# SCT2XX0_STEP-DOWM.net
KiCad netlist of a schematic drawn in Altium Designer
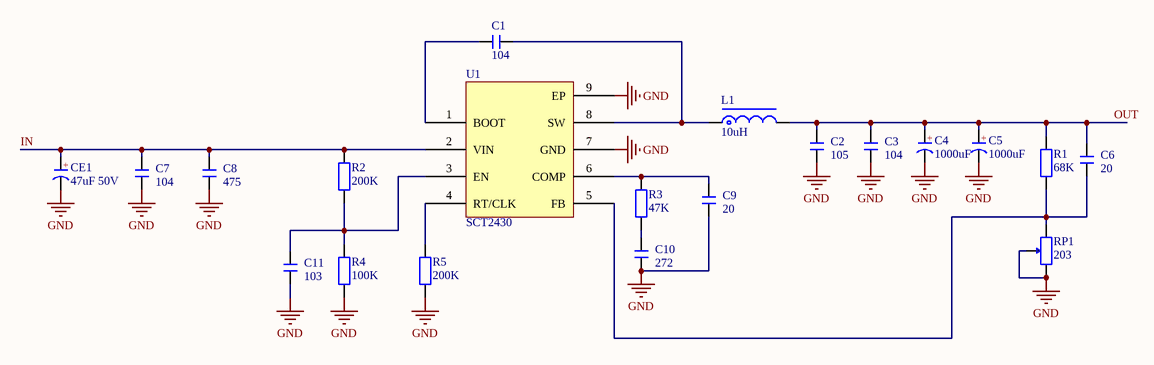
[diagram p0: SCT2XX0 STEP-DOWM.SchDoc]

(export (version "E")
  (design (tool "Eeschema 10.0.6"))
  (components
    (comp (ref "C1")
      (value "104")
      (footprint "C 0805_L")
      (description "贴片电容")
      (libsource (lib "01 - 电容-电阻-电感") (part "C"))
    )
    (comp (ref "C2")
      (value "105")
      (footprint "C 0805_L")
      (description "贴片电容")
      (libsource (lib "01 - 电容-电阻-电感") (part "C"))
    )
    (comp (ref "C3")
      (value "104")
      (footprint "C 0805_L")
      (description "贴片电容")
      (libsource (lib "01 - 电容-电阻-电感") (part "C"))
    )
    (comp (ref "C4")
      (value "1000uF")
      (footprint "CAP 7.5*16*25")
      (description "直插电解电容")
      (libsource (lib "01 - 电容-电阻-电感") (part "CE"))
    )
    (comp (ref "C5")
      (value "1000uF")
      (footprint "CAP 5.0*12.5*20")
      (description "直插电解电容")
      (libsource (lib "01 - 电容-电阻-电感") (part "CE"))
    )
    (comp (ref "C6")
      (value "20")
      (footprint "C 0805_L")
      (description "贴片电容")
      (libsource (lib "01 - 电容-电阻-电感") (part "C"))
    )
    (comp (ref "C7")
      (value "104")
      (footprint "C 0805_L")
      (description "贴片电容")
      (libsource (lib "01 - 电容-电阻-电感") (part "C"))
    )
    (comp (ref "C8")
      (value "475")
      (footprint "C 0805_L")
      (description "贴片电容")
      (libsource (lib "01 - 电容-电阻-电感") (part "C"))
    )
    (comp (ref "C9")
      (value "20")
      (footprint "C 0805_L")
      (description "贴片电容")
      (libsource (lib "01 - 电容-电阻-电感") (part "C"))
    )
    (comp (ref "C10")
      (value "272")
      (footprint "C 0805_L")
      (description "贴片电容")
      (libsource (lib "01 - 电容-电阻-电感") (part "C"))
    )
    (comp (ref "C11")
      (value "103")
      (footprint "C 0805_L")
      (description "贴片电容")
      (libsource (lib "01 - 电容-电阻-电感") (part "C"))
    )
    (comp (ref "CE1")
      (value "47uF 50V")
      (footprint "CM C(5*5.4)")
      (description "贴片电解电容")
      (libsource (lib "01 - 电容-电阻-电感") (part "CE_SMD"))
    )
    (comp (ref "L1")
      (value "10uH")
      (footprint "CDRH127")
      (description "功率屏蔽电感")
      (libsource (lib "01 - 电容-电阻-电感") (part "L-CDRH"))
    )
    (comp (ref "R1")
      (value "68K")
      (footprint "R 0805_L")
      (description "贴片电阻")
      (libsource (lib "01 - 电容-电阻-电感") (part "R"))
    )
    (comp (ref "R2")
      (value "200K")
      (footprint "R 0805_L")
      (description "贴片电阻")
      (libsource (lib "01 - 电容-电阻-电感") (part "R"))
    )
    (comp (ref "R3")
      (value "47K")
      (footprint "R 0805_L")
      (description "贴片电阻")
      (libsource (lib "01 - 电容-电阻-电感") (part "R"))
    )
    (comp (ref "R4")
      (value "100K")
      (footprint "R 0805_L")
      (description "贴片电阻")
      (libsource (lib "01 - 电容-电阻-电感") (part "R"))
    )
    (comp (ref "R5")
      (value "200K")
      (footprint "R 0805_L")
      (description "贴片电阻")
      (libsource (lib "01 - 电容-电阻-电感") (part "R"))
    )
    (comp (ref "RP1")
      (value "203")
      (footprint "3296W")
      (description "单联电位器")
      (libsource (lib "01 - 电容-电阻-电感") (part "RP"))
    )
    (comp (ref "U1") (value "SCT2430") (footprint "ESOP8_N") (libsource (lib "10 - DC-DC") (part "SCT2430")))
  )
  (nets
    (net (code "1") (name "/IN") (class "Default")
      (node (ref "C7") (pin "2") (pinfunction "2_2") (pintype "passive"))
      (node (ref "C8") (pin "2") (pinfunction "2_2") (pintype "passive"))
      (node (ref "CE1") (pin "1") (pinfunction "A_1") (pintype "passive"))
      (node (ref "R2") (pin "2") (pinfunction "2_2") (pintype "passive"))
      (node (ref "U1") (pin "2") (pinfunction "VIN_2") (pintype "passive"))
    )
    (net (code "2") (name "/OUT") (class "Default")
      (node (ref "C2") (pin "2") (pinfunction "2_2") (pintype "passive"))
      (node (ref "C3") (pin "2") (pinfunction "2_2") (pintype "passive"))
      (node (ref "C4") (pin "1") (pinfunction "A_1") (pintype "passive"))
      (node (ref "C5") (pin "1") (pinfunction "A_1") (pintype "passive"))
      (node (ref "C6") (pin "2") (pinfunction "2_2") (pintype "passive"))
      (node (ref "L1") (pin "2") (pinfunction "2_2") (pintype "passive"))
      (node (ref "R1") (pin "2") (pinfunction "2_2") (pintype "passive"))
    )
    (net (code "3") (name "GND") (class "Default")
      (node (ref "C10") (pin "1") (pinfunction "1_1") (pintype "passive"))
      (node (ref "C11") (pin "1") (pinfunction "1_1") (pintype "passive"))
      (node (ref "C2") (pin "1") (pinfunction "1_1") (pintype "passive"))
      (node (ref "C3") (pin "1") (pinfunction "1_1") (pintype "passive"))
      (node (ref "C4") (pin "2") (pinfunction "K_2") (pintype "passive"))
      (node (ref "C5") (pin "2") (pinfunction "K_2") (pintype "passive"))
      (node (ref "C7") (pin "1") (pinfunction "1_1") (pintype "passive"))
      (node (ref "C8") (pin "1") (pinfunction "1_1") (pintype "passive"))
      (node (ref "C9") (pin "1") (pinfunction "1_1") (pintype "passive"))
      (node (ref "CE1") (pin "2") (pinfunction "K_2") (pintype "passive"))
      (node (ref "R4") (pin "1") (pinfunction "1_1") (pintype "passive"))
      (node (ref "R5") (pin "1") (pinfunction "1_1") (pintype "passive"))
      (node (ref "RP1") (pin "1") (pinfunction "1_1") (pintype "passive"))
      (node (ref "RP1") (pin "2") (pinfunction "2_2") (pintype "passive"))
      (node (ref "U1") (pin "7") (pinfunction "GND_7") (pintype "passive"))
      (node (ref "U1") (pin "9") (pinfunction "EP_9") (pintype "passive"))
    )
    (net (code "4") (name "Net-(C10-Pad2)") (class "Default")
      (node (ref "C10") (pin "2") (pinfunction "2_2") (pintype "passive"))
      (node (ref "R3") (pin "1") (pinfunction "1_1") (pintype "passive"))
    )
    (net (code "5") (name "Net-(U1-BOOT)") (class "Default")
      (node (ref "C1") (pin "1") (pinfunction "1_1") (pintype "passive"))
      (node (ref "U1") (pin "1") (pinfunction "BOOT_1") (pintype "passive"))
    )
    (net (code "6") (name "Net-(U1-COMP)") (class "Default")
      (node (ref "C9") (pin "2") (pinfunction "2_2") (pintype "passive"))
      (node (ref "R3") (pin "2") (pinfunction "2_2") (pintype "passive"))
      (node (ref "U1") (pin "6") (pinfunction "COMP_6") (pintype "passive"))
    )
    (net (code "7") (name "Net-(U1-EN)") (class "Default")
      (node (ref "C11") (pin "2") (pinfunction "2_2") (pintype "passive"))
      (node (ref "R2") (pin "1") (pinfunction "1_1") (pintype "passive"))
      (node (ref "R4") (pin "2") (pinfunction "2_2") (pintype "passive"))
      (node (ref "U1") (pin "3") (pinfunction "EN_3") (pintype "passive"))
    )
    (net (code "8") (name "Net-(U1-FB)") (class "Default")
      (node (ref "C6") (pin "1") (pinfunction "1_1") (pintype "passive"))
      (node (ref "R1") (pin "1") (pinfunction "1_1") (pintype "passive"))
      (node (ref "RP1") (pin "3") (pinfunction "3_3") (pintype "passive"))
      (node (ref "U1") (pin "5") (pinfunction "FB_5") (pintype "passive"))
    )
    (net (code "9") (name "Net-(U1-RT{slash}CLK)") (class "Default")
      (node (ref "R5") (pin "2") (pinfunction "2_2") (pintype "passive"))
      (node (ref "U1") (pin "4") (pinfunction "RT/CLK_4") (pintype "passive"))
    )
    (net (code "10") (name "Net-(U1-SW)") (class "Default")
      (node (ref "C1") (pin "2") (pinfunction "2_2") (pintype "passive"))
      (node (ref "L1") (pin "1") (pinfunction "1_1") (pintype "passive"))
      (node (ref "U1") (pin "8") (pinfunction "SW_8") (pintype "passive"))
    )
  )
)
